# Signal_source_V1p0.net
KiCad netlist of a schematic drawn in EAGLE
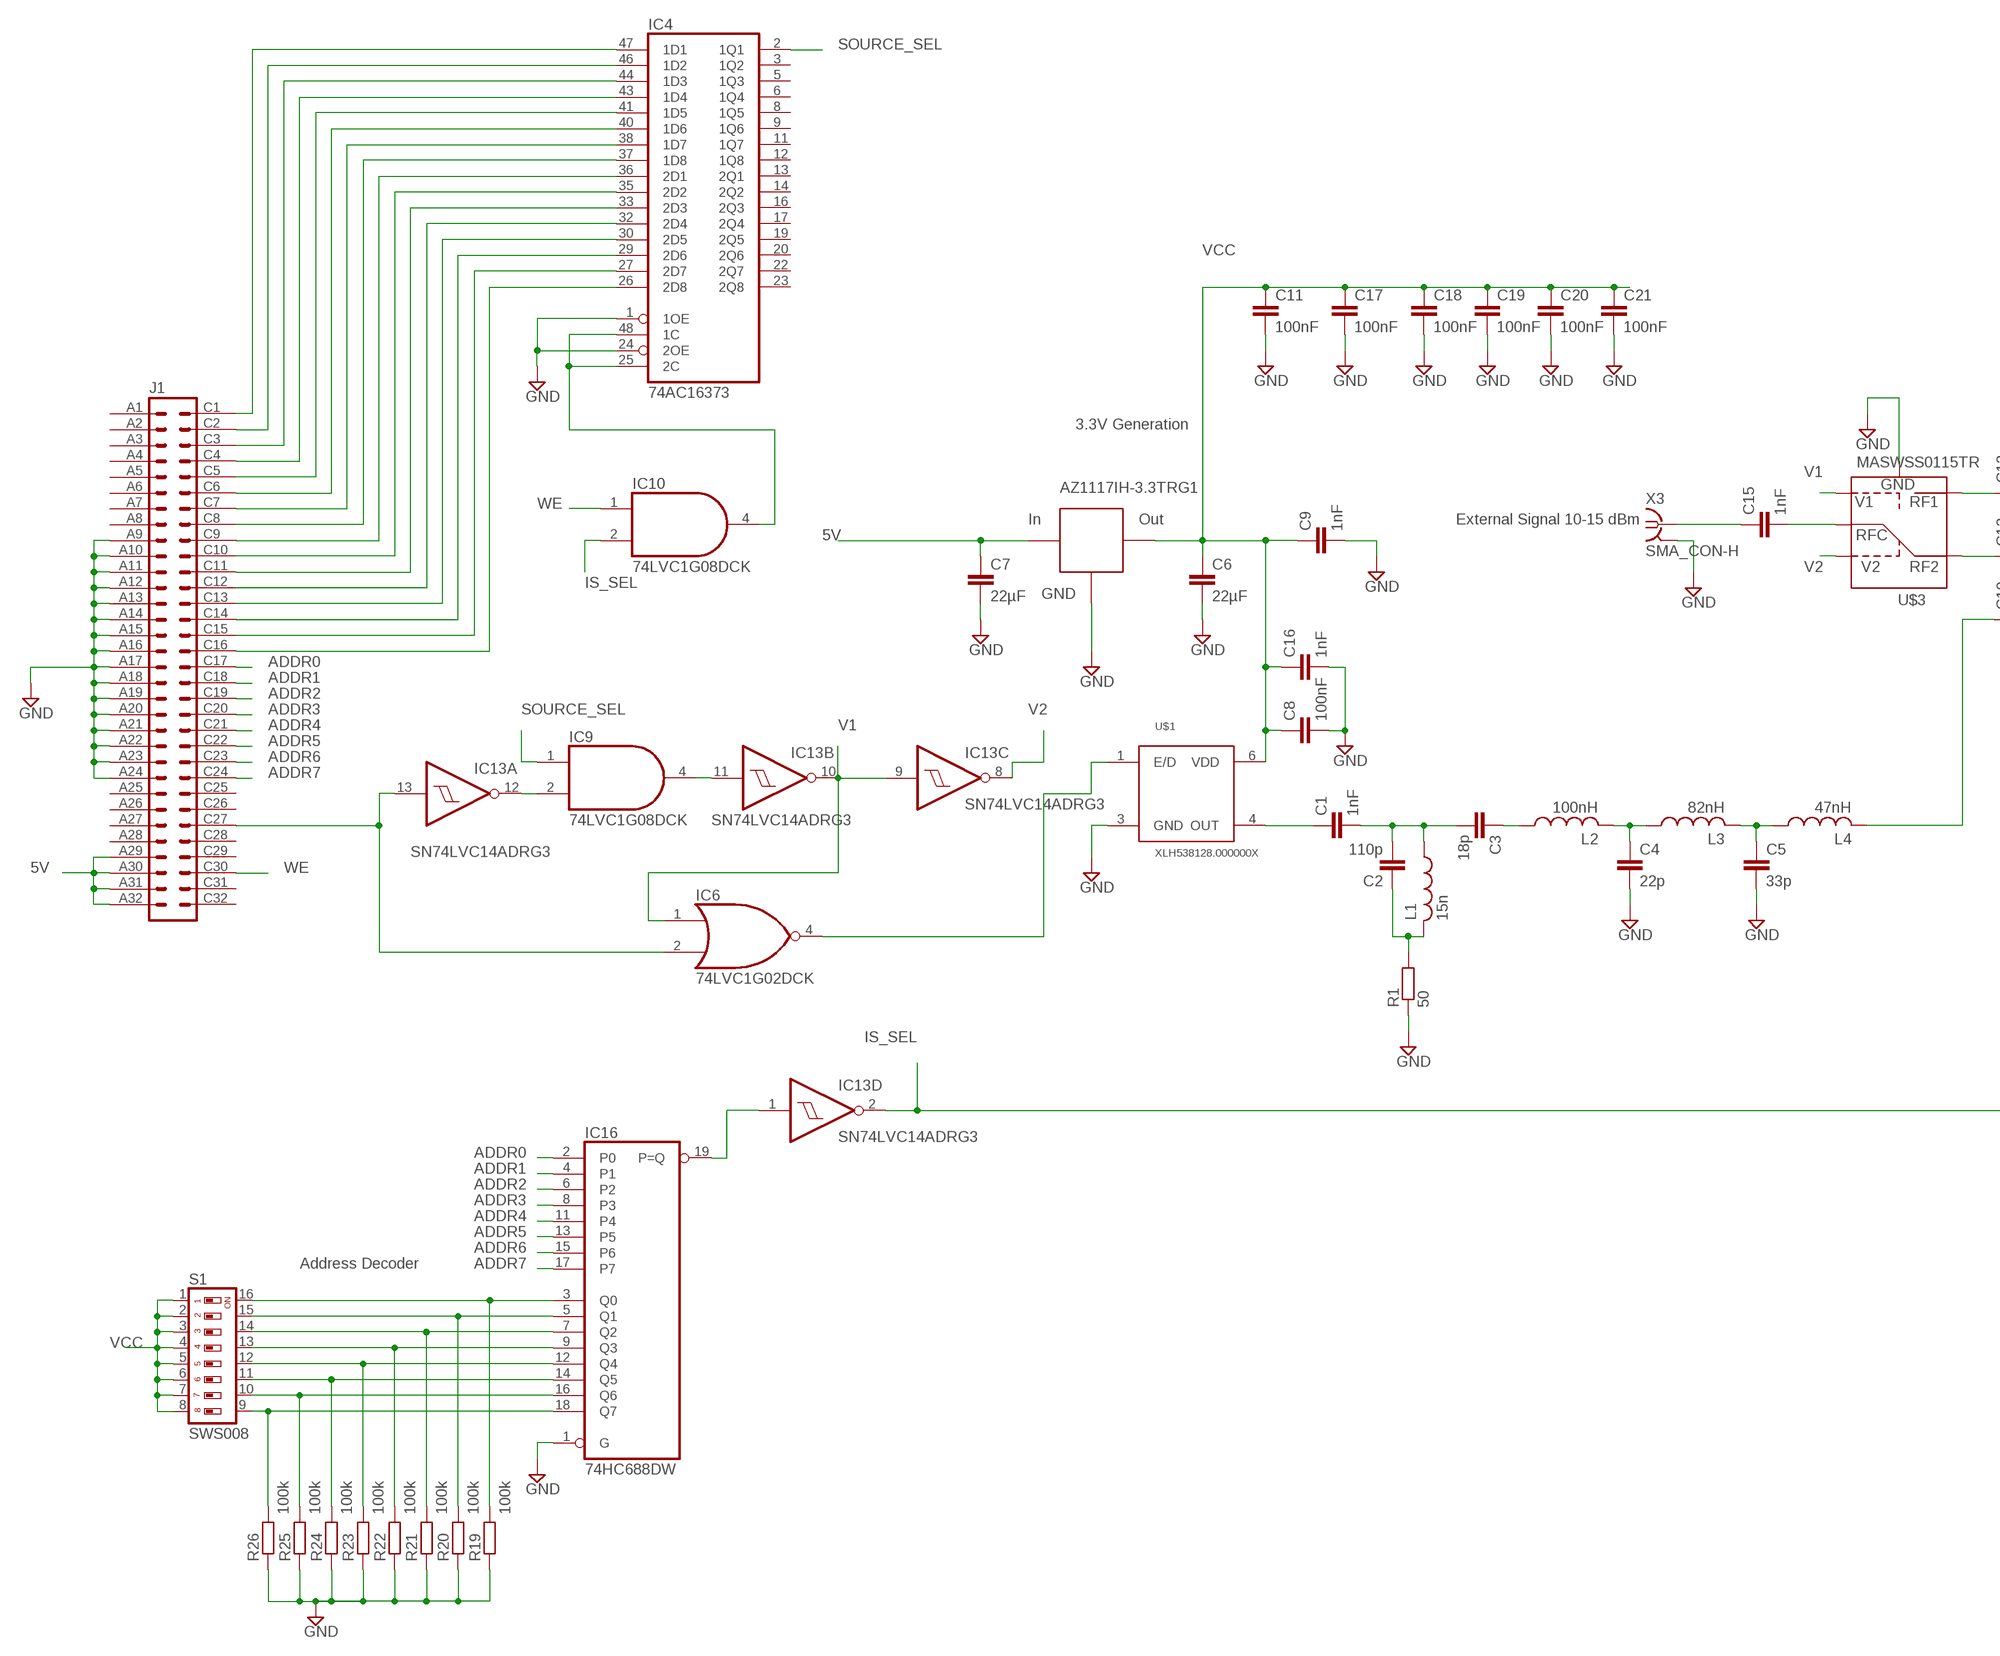
[diagram p0: schematic, sheet 1, part 1 of 2]
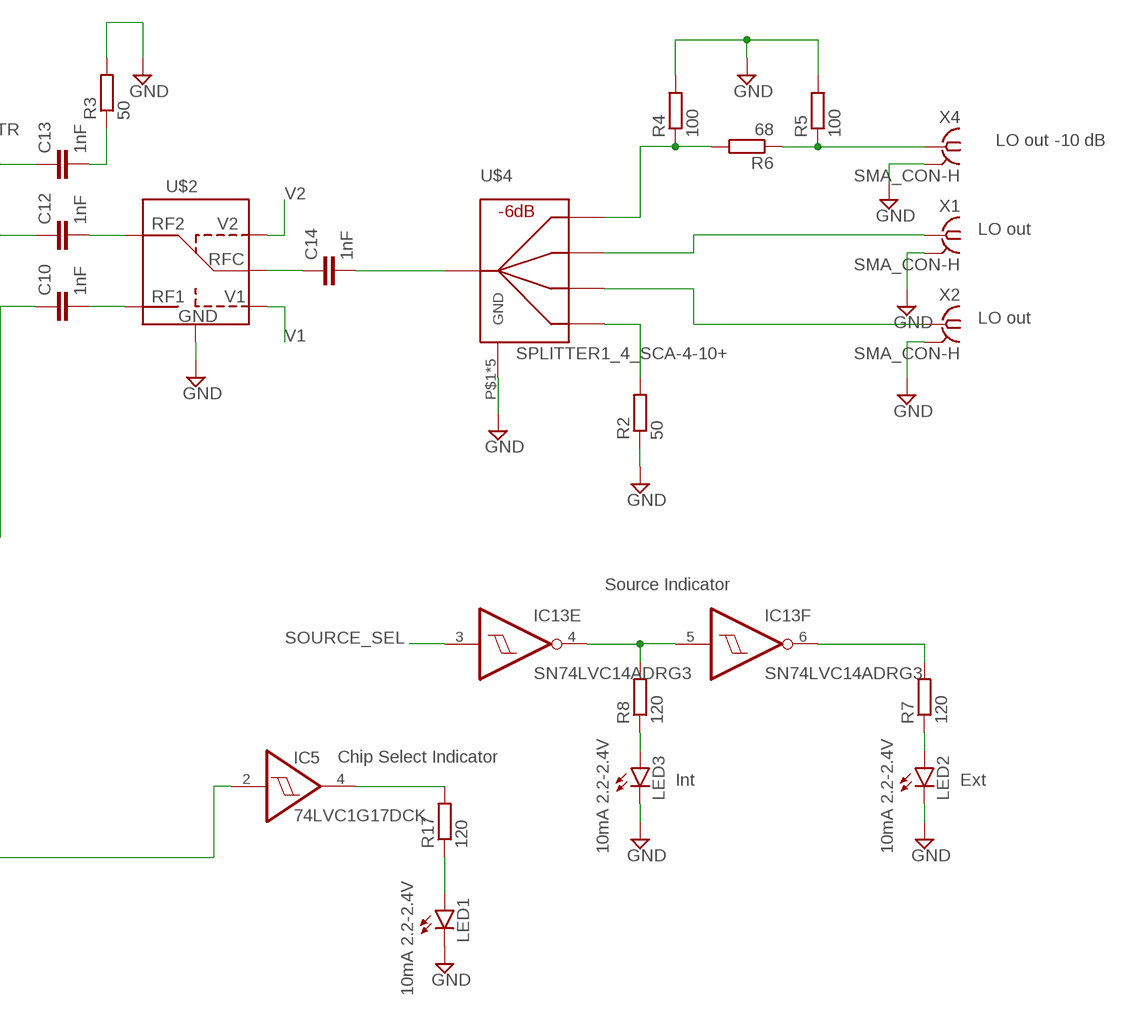
[diagram p1: schematic, sheet 1, part 2 of 2]

(export (version "E")
  (design (tool "Eeschema 10.0.6"))
  (components
    (comp (ref "C1")
      (value "1nF")
      (footprint "eagle-import:C0805")
      (libsource (lib "eagle-import") (part "C-EUC0805"))
    )
    (comp (ref "C2")
      (value "110p")
      (footprint "eagle-import:C0805")
      (libsource (lib "eagle-import") (part "C-EUC0805"))
    )
    (comp (ref "C3")
      (value "18p")
      (footprint "eagle-import:C0805")
      (libsource (lib "eagle-import") (part "C-EUC0805"))
    )
    (comp (ref "C4")
      (value "22p")
      (footprint "eagle-import:C0805")
      (libsource (lib "eagle-import") (part "C-EUC0805"))
    )
    (comp (ref "C5")
      (value "33p")
      (footprint "eagle-import:C0805")
      (libsource (lib "eagle-import") (part "C-EUC0805"))
    )
    (comp (ref "C6")
      (value "22µF")
      (footprint "eagle-import:C1206")
      (libsource (lib "eagle-import") (part "C-EUC1206"))
    )
    (comp (ref "C7")
      (value "22µF")
      (footprint "eagle-import:C1206")
      (libsource (lib "eagle-import") (part "C-EUC1206"))
    )
    (comp (ref "C8")
      (value "100nF")
      (footprint "eagle-import:C1206")
      (libsource (lib "eagle-import") (part "C-EUC1206"))
    )
    (comp (ref "C9")
      (value "1nF")
      (footprint "eagle-import:C0805")
      (libsource (lib "eagle-import") (part "C-EUC0805"))
    )
    (comp (ref "C10")
      (value "1nF")
      (footprint "eagle-import:C0805")
      (libsource (lib "eagle-import") (part "C-EUC0805"))
    )
    (comp (ref "C11")
      (value "100nF")
      (footprint "eagle-import:C1206")
      (libsource (lib "eagle-import") (part "C-EUC1206"))
    )
    (comp (ref "C12")
      (value "1nF")
      (footprint "eagle-import:C0805")
      (libsource (lib "eagle-import") (part "C-EUC0805"))
    )
    (comp (ref "C13")
      (value "1nF")
      (footprint "eagle-import:C0805")
      (libsource (lib "eagle-import") (part "C-EUC0805"))
    )
    (comp (ref "C14")
      (value "1nF")
      (footprint "eagle-import:C0805")
      (libsource (lib "eagle-import") (part "C-EUC0805"))
    )
    (comp (ref "C15")
      (value "1nF")
      (footprint "eagle-import:C0805")
      (libsource (lib "eagle-import") (part "C-EUC0805"))
    )
    (comp (ref "C16")
      (value "1nF")
      (footprint "eagle-import:C0805")
      (libsource (lib "eagle-import") (part "C-EUC0805"))
    )
    (comp (ref "C17")
      (value "100nF")
      (footprint "eagle-import:C1206")
      (libsource (lib "eagle-import") (part "C-EUC1206"))
    )
    (comp (ref "C18")
      (value "100nF")
      (footprint "eagle-import:C1206")
      (libsource (lib "eagle-import") (part "C-EUC1206"))
    )
    (comp (ref "C19")
      (value "100nF")
      (footprint "eagle-import:C1206")
      (libsource (lib "eagle-import") (part "C-EUC1206"))
    )
    (comp (ref "C20")
      (value "100nF")
      (footprint "eagle-import:C1206")
      (libsource (lib "eagle-import") (part "C-EUC1206"))
    )
    (comp (ref "C21")
      (value "100nF")
      (footprint "eagle-import:C1206")
      (libsource (lib "eagle-import") (part "C-EUC1206"))
    )
    (comp (ref "IC4")
      (value "74AC16373")
      (footprint "eagle-import:SSOP48DL")
      (libsource (lib "eagle-import") (part "74AC16373"))
    )
    (comp (ref "IC5")
      (value "74LVC1G17DCK")
      (footprint "eagle-import:SC70-5")
      (libsource (lib "eagle-import") (part "741G17DCKLVC"))
    )
    (comp (ref "IC6")
      (value "74LVC1G02DCK")
      (footprint "eagle-import:SC70-5")
      (libsource (lib "eagle-import") (part "741G02DCKLVC"))
    )
    (comp (ref "IC9")
      (value "74LVC1G08DCK")
      (footprint "eagle-import:SC70-5")
      (libsource (lib "eagle-import") (part "741G08DCKLVC"))
    )
    (comp (ref "IC10")
      (value "74LVC1G08DCK")
      (footprint "eagle-import:SC70-5")
      (libsource (lib "eagle-import") (part "741G08DCKLVC"))
    )
    (comp (ref "IC13")
      (value "SN74LVC14ADRG3")
      (footprint "eagle-import:SO14")
      (libsource (lib "eagle-import") (part "7414D"))
    )
    (comp (ref "IC16")
      (value "74HC688DW")
      (footprint "eagle-import:SO20W")
      (libsource (lib "eagle-import") (part "74688DWHC"))
    )
    (comp (ref "J1")
      (value "VG64P")
      (footprint "eagle-import:VG64P")
      (libsource (lib "eagle-import") (part "VG64P"))
    )
    (comp (ref "L1")
      (value "15n")
      (footprint "eagle-import:L3225M")
      (libsource (lib "eagle-import") (part "L-USL3225M"))
    )
    (comp (ref "L2")
      (value "100nH")
      (footprint "eagle-import:L3225M")
      (libsource (lib "eagle-import") (part "L-USL3225M"))
    )
    (comp (ref "L3")
      (value "82nH")
      (footprint "eagle-import:L3225M")
      (libsource (lib "eagle-import") (part "L-USL3225M"))
    )
    (comp (ref "L4")
      (value "47nH")
      (footprint "eagle-import:L3225M")
      (libsource (lib "eagle-import") (part "L-USL3225M"))
    )
    (comp (ref "LED1")
      (value "10mA 2.2-2.4V")
      (footprint "eagle-import:LED3MM")
      (libsource (lib "eagle-import") (part "LED3MM"))
    )
    (comp (ref "LED2")
      (value "10mA 2.2-2.4V")
      (footprint "eagle-import:LED3MM")
      (libsource (lib "eagle-import") (part "LED3MM"))
    )
    (comp (ref "LED3")
      (value "10mA 2.2-2.4V")
      (footprint "eagle-import:LED3MM")
      (libsource (lib "eagle-import") (part "LED3MM"))
    )
    (comp (ref "R1")
      (value "50")
      (footprint "eagle-import:R0805")
      (libsource (lib "eagle-import") (part "R-EU_R0805"))
    )
    (comp (ref "R2")
      (value "50")
      (footprint "eagle-import:R0805")
      (libsource (lib "eagle-import") (part "R-EU_R0805"))
    )
    (comp (ref "R3")
      (value "50")
      (footprint "eagle-import:R0805")
      (libsource (lib "eagle-import") (part "R-EU_R0805"))
    )
    (comp (ref "R4")
      (value "100")
      (footprint "eagle-import:R0805")
      (libsource (lib "eagle-import") (part "R-EU_R0805"))
    )
    (comp (ref "R5")
      (value "100")
      (footprint "eagle-import:R0805")
      (libsource (lib "eagle-import") (part "R-EU_R0805"))
    )
    (comp (ref "R6")
      (value "68")
      (footprint "eagle-import:R0805")
      (libsource (lib "eagle-import") (part "R-EU_R0805"))
    )
    (comp (ref "R7")
      (value "120")
      (footprint "eagle-import:R0603")
      (libsource (lib "eagle-import") (part "R-EU_R0603"))
    )
    (comp (ref "R8")
      (value "120")
      (footprint "eagle-import:R0603")
      (libsource (lib "eagle-import") (part "R-EU_R0603"))
    )
    (comp (ref "R17")
      (value "120")
      (footprint "eagle-import:R0603")
      (libsource (lib "eagle-import") (part "R-EU_R0603"))
    )
    (comp (ref "R19")
      (value "100k")
      (footprint "eagle-import:R0603")
      (libsource (lib "eagle-import") (part "R-EU_R0603"))
    )
    (comp (ref "R20")
      (value "100k")
      (footprint "eagle-import:R0603")
      (libsource (lib "eagle-import") (part "R-EU_R0603"))
    )
    (comp (ref "R21")
      (value "100k")
      (footprint "eagle-import:R0603")
      (libsource (lib "eagle-import") (part "R-EU_R0603"))
    )
    (comp (ref "R22")
      (value "100k")
      (footprint "eagle-import:R0603")
      (libsource (lib "eagle-import") (part "R-EU_R0603"))
    )
    (comp (ref "R23")
      (value "100k")
      (footprint "eagle-import:R0603")
      (libsource (lib "eagle-import") (part "R-EU_R0603"))
    )
    (comp (ref "R24")
      (value "100k")
      (footprint "eagle-import:R0603")
      (libsource (lib "eagle-import") (part "R-EU_R0603"))
    )
    (comp (ref "R25")
      (value "100k")
      (footprint "eagle-import:R0603")
      (libsource (lib "eagle-import") (part "R-EU_R0603"))
    )
    (comp (ref "R26")
      (value "100k")
      (footprint "eagle-import:R0603")
      (libsource (lib "eagle-import") (part "R-EU_R0603"))
    )
    (comp (ref "S1")
      (value "SWS008")
      (footprint "eagle-import:SMS-008")
      (libsource (lib "eagle-import") (part "SWS008"))
    )
    (comp (ref "U$1")
      (value "XLH538128.000000X")
      (footprint "eagle-import:5.0X3.2_XO")
      (libsource (lib "eagle-import") (part "XLH538128.000000X"))
    )
    (comp (ref "U$2")
      (value "MASWSS0115TR")
      (footprint "eagle-import:SC70-6")
      (libsource (lib "eagle-import") (part "SPDT_SC70-6"))
    )
    (comp (ref "U$3")
      (value "MASWSS0115TR")
      (footprint "eagle-import:SC70-6")
      (libsource (lib "eagle-import") (part "SPDT_SC70-6"))
    )
    (comp (ref "U$4")
      (value "SPLITTER1_4_SCA-4-10+")
      (footprint "eagle-import:SCA-4-10+")
      (libsource (lib "eagle-import") (part "SPLITTER1_4_SCA-4-10+"))
    )
    (comp (ref "U$9")
      (value "AZ1117IH-3.3TRG1")
      (footprint "eagle-import:SOT223")
      (libsource (lib "eagle-import") (part "LT1117"))
    )
    (comp (ref "X1")
      (value "SMA_CON-H")
      (footprint "eagle-import:BU-SMA-H")
      (libsource (lib "eagle-import") (part "SMA_CON-H"))
    )
    (comp (ref "X2")
      (value "SMA_CON-H")
      (footprint "eagle-import:BU-SMA-H")
      (libsource (lib "eagle-import") (part "SMA_CON-H"))
    )
    (comp (ref "X3")
      (value "SMA_CON-H")
      (footprint "eagle-import:BU-SMA-H")
      (libsource (lib "eagle-import") (part "SMA_CON-H"))
    )
    (comp (ref "X4")
      (value "SMA_CON-H")
      (footprint "eagle-import:BU-SMA-H")
      (libsource (lib "eagle-import") (part "SMA_CON-H"))
    )
  )
  (nets
    (net (code "1") (name "/5V") (class "Default")
      (node (ref "C7") (pin "1") (pinfunction "1_1") (pintype "passive"))
      (node (ref "J1") (pin "A29") (pinfunction "A29_A29") (pintype "passive"))
      (node (ref "J1") (pin "A30") (pinfunction "A30_A30") (pintype "passive"))
      (node (ref "J1") (pin "A31") (pinfunction "A31_A31") (pintype "passive"))
      (node (ref "J1") (pin "A32") (pinfunction "A32_A32") (pintype "passive"))
      (node (ref "U$9") (pin "3") (pinfunction "IN_3") (pintype "bidirectional"))
    )
    (net (code "2") (name "/ADDR0") (class "Default")
      (node (ref "IC16") (pin "2") (pinfunction "P0_2") (pintype "input"))
      (node (ref "J1") (pin "C17") (pinfunction "C17_C17") (pintype "passive"))
    )
    (net (code "3") (name "/ADDR1") (class "Default")
      (node (ref "IC16") (pin "4") (pinfunction "P1_4") (pintype "input"))
      (node (ref "J1") (pin "C18") (pinfunction "C18_C18") (pintype "passive"))
    )
    (net (code "4") (name "/ADDR2") (class "Default")
      (node (ref "IC16") (pin "6") (pinfunction "P2_6") (pintype "input"))
      (node (ref "J1") (pin "C19") (pinfunction "C19_C19") (pintype "passive"))
    )
    (net (code "5") (name "/ADDR3") (class "Default")
      (node (ref "IC16") (pin "8") (pinfunction "P3_8") (pintype "input"))
      (node (ref "J1") (pin "C20") (pinfunction "C20_C20") (pintype "passive"))
    )
    (net (code "6") (name "/ADDR4") (class "Default")
      (node (ref "IC16") (pin "11") (pinfunction "P4_11") (pintype "input"))
      (node (ref "J1") (pin "C21") (pinfunction "C21_C21") (pintype "passive"))
    )
    (net (code "7") (name "/ADDR5") (class "Default")
      (node (ref "IC16") (pin "13") (pinfunction "P5_13") (pintype "input"))
      (node (ref "J1") (pin "C22") (pinfunction "C22_C22") (pintype "passive"))
    )
    (net (code "8") (name "/ADDR6") (class "Default")
      (node (ref "IC16") (pin "15") (pinfunction "P6_15") (pintype "input"))
      (node (ref "J1") (pin "C23") (pinfunction "C23_C23") (pintype "passive"))
    )
    (net (code "9") (name "/ADDR7") (class "Default")
      (node (ref "IC16") (pin "17") (pinfunction "P7_17") (pintype "input"))
      (node (ref "J1") (pin "C24") (pinfunction "C24_C24") (pintype "passive"))
    )
    (net (code "10") (name "/IS_SEL") (class "Default")
      (node (ref "IC10") (pin "2") (pinfunction "I1_2") (pintype "input"))
      (node (ref "IC13") (pin "2") (pinfunction "O_2") (pintype "output"))
      (node (ref "IC5") (pin "2") (pinfunction "I_2") (pintype "input"))
    )
    (net (code "11") (name "/SOURCE_SEL") (class "Default")
      (node (ref "IC13") (pin "3") (pinfunction "I_3") (pintype "input"))
      (node (ref "IC4") (pin "2") (pinfunction "1Q1_2") (pintype "tri_state"))
      (node (ref "IC9") (pin "1") (pinfunction "I0_1") (pintype "input"))
    )
    (net (code "12") (name "/V1") (class "Default")
      (node (ref "IC13") (pin "10") (pinfunction "O_10") (pintype "output"))
      (node (ref "IC13") (pin "9") (pinfunction "I_9") (pintype "input"))
      (node (ref "IC6") (pin "1") (pinfunction "I0_1") (pintype "input"))
      (node (ref "U$2") (pin "6") (pinfunction "V1_6") (pintype "bidirectional"))
      (node (ref "U$3") (pin "6") (pinfunction "V1_6") (pintype "bidirectional"))
    )
    (net (code "13") (name "/V2") (class "Default")
      (node (ref "IC13") (pin "8") (pinfunction "O_8") (pintype "output"))
      (node (ref "U$2") (pin "4") (pinfunction "V2_4") (pintype "bidirectional"))
      (node (ref "U$3") (pin "4") (pinfunction "V2_4") (pintype "bidirectional"))
    )
    (net (code "14") (name "/VCC") (class "Default")
      (node (ref "C11") (pin "1") (pinfunction "1_1") (pintype "passive"))
      (node (ref "C16") (pin "1") (pinfunction "1_1") (pintype "passive"))
      (node (ref "C17") (pin "1") (pinfunction "1_1") (pintype "passive"))
      (node (ref "C18") (pin "1") (pinfunction "1_1") (pintype "passive"))
      (node (ref "C19") (pin "1") (pinfunction "1_1") (pintype "passive"))
      (node (ref "C20") (pin "1") (pinfunction "1_1") (pintype "passive"))
      (node (ref "C21") (pin "1") (pinfunction "1_1") (pintype "passive"))
      (node (ref "C6") (pin "1") (pinfunction "1_1") (pintype "passive"))
      (node (ref "C8") (pin "1") (pinfunction "1_1") (pintype "passive"))
      (node (ref "C9") (pin "1") (pinfunction "1_1") (pintype "passive"))
      (node (ref "S1") (pin "1") (pinfunction "1_1") (pintype "passive"))
      (node (ref "S1") (pin "2") (pinfunction "2_2") (pintype "passive"))
      (node (ref "S1") (pin "3") (pinfunction "3_3") (pintype "passive"))
      (node (ref "S1") (pin "4") (pinfunction "4_4") (pintype "passive"))
      (node (ref "S1") (pin "5") (pinfunction "5_5") (pintype "passive"))
      (node (ref "S1") (pin "6") (pinfunction "6_6") (pintype "passive"))
      (node (ref "S1") (pin "7") (pinfunction "7_7") (pintype "passive"))
      (node (ref "S1") (pin "8") (pinfunction "8_8") (pintype "passive"))
      (node (ref "U$1") (pin "6") (pinfunction "VDD_6") (pintype "bidirectional"))
      (node (ref "U$9") (pin "2") (pinfunction "OUT_2") (pintype "bidirectional"))
      (node (ref "U$9") (pin "4") (pinfunction "OUT_4") (pintype "bidirectional"))
    )
    (net (code "15") (name "/WE") (class "Default")
      (node (ref "IC10") (pin "1") (pinfunction "I0_1") (pintype "input"))
      (node (ref "J1") (pin "C30") (pinfunction "C30_C30") (pintype "passive"))
    )
    (net (code "16") (name "GND") (class "Default")
      (node (ref "C11") (pin "2") (pinfunction "2_2") (pintype "passive"))
      (node (ref "C16") (pin "2") (pinfunction "2_2") (pintype "passive"))
      (node (ref "C17") (pin "2") (pinfunction "2_2") (pintype "passive"))
      (node (ref "C18") (pin "2") (pinfunction "2_2") (pintype "passive"))
      (node (ref "C19") (pin "2") (pinfunction "2_2") (pintype "passive"))
      (node (ref "C20") (pin "2") (pinfunction "2_2") (pintype "passive"))
      (node (ref "C21") (pin "2") (pinfunction "2_2") (pintype "passive"))
      (node (ref "C4") (pin "2") (pinfunction "2_2") (pintype "passive"))
      (node (ref "C5") (pin "2") (pinfunction "2_2") (pintype "passive"))
      (node (ref "C6") (pin "2") (pinfunction "2_2") (pintype "passive"))
      (node (ref "C7") (pin "2") (pinfunction "2_2") (pintype "passive"))
      (node (ref "C8") (pin "2") (pinfunction "2_2") (pintype "passive"))
      (node (ref "C9") (pin "2") (pinfunction "2_2") (pintype "passive"))
      (node (ref "IC16") (pin "1") (pinfunction "G_1") (pintype "input"))
      (node (ref "IC4") (pin "1") (pinfunction "1OE_1") (pintype "input"))
      (node (ref "IC4") (pin "24") (pinfunction "2OE_24") (pintype "input"))
      (node (ref "J1") (pin "A10") (pinfunction "A10_A10") (pintype "passive"))
      (node (ref "J1") (pin "A11") (pinfunction "A11_A11") (pintype "passive"))
      (node (ref "J1") (pin "A12") (pinfunction "A12_A12") (pintype "passive"))
      (node (ref "J1") (pin "A13") (pinfunction "A13_A13") (pintype "passive"))
      (node (ref "J1") (pin "A14") (pinfunction "A14_A14") (pintype "passive"))
      (node (ref "J1") (pin "A15") (pinfunction "A15_A15") (pintype "passive"))
      (node (ref "J1") (pin "A16") (pinfunction "A16_A16") (pintype "passive"))
      (node (ref "J1") (pin "A17") (pinfunction "A17_A17") (pintype "passive"))
      (node (ref "J1") (pin "A18") (pinfunction "A18_A18") (pintype "passive"))
      (node (ref "J1") (pin "A19") (pinfunction "A19_A19") (pintype "passive"))
      (node (ref "J1") (pin "A20") (pinfunction "A20_A20") (pintype "passive"))
      (node (ref "J1") (pin "A21") (pinfunction "A21_A21") (pintype "passive"))
      (node (ref "J1") (pin "A22") (pinfunction "A22_A22") (pintype "passive"))
      (node (ref "J1") (pin "A23") (pinfunction "A23_A23") (pintype "passive"))
      (node (ref "J1") (pin "A24") (pinfunction "A24_A24") (pintype "passive"))
      (node (ref "J1") (pin "A9") (pinfunction "A9_A9") (pintype "passive"))
      (node (ref "LED1") (pin "K") (pinfunction "C_K") (pintype "passive"))
      (node (ref "LED2") (pin "K") (pinfunction "C_K") (pintype "passive"))
      (node (ref "LED3") (pin "K") (pinfunction "C_K") (pintype "passive"))
      (node (ref "R1") (pin "1") (pinfunction "1_1") (pintype "passive"))
      (node (ref "R19") (pin "1") (pinfunction "1_1") (pintype "passive"))
      (node (ref "R2") (pin "1") (pinfunction "1_1") (pintype "passive"))
      (node (ref "R20") (pin "1") (pinfunction "1_1") (pintype "passive"))
      (node (ref "R21") (pin "1") (pinfunction "1_1") (pintype "passive"))
      (node (ref "R22") (pin "1") (pinfunction "1_1") (pintype "passive"))
      (node (ref "R23") (pin "1") (pinfunction "1_1") (pintype "passive"))
      (node (ref "R24") (pin "1") (pinfunction "1_1") (pintype "passive"))
      (node (ref "R25") (pin "1") (pinfunction "1_1") (pintype "passive"))
      (node (ref "R26") (pin "1") (pinfunction "1_1") (pintype "passive"))
      (node (ref "R3") (pin "2") (pinfunction "2_2") (pintype "passive"))
      (node (ref "R4") (pin "2") (pinfunction "2_2") (pintype "passive"))
      (node (ref "R5") (pin "2") (pinfunction "2_2") (pintype "passive"))
      (node (ref "U$1") (pin "3") (pinfunction "GND_3") (pintype "bidirectional"))
      (node (ref "U$2") (pin "2") (pinfunction "GND_2") (pintype "bidirectional"))
      (node (ref "U$3") (pin "2") (pinfunction "GND_2") (pintype "bidirectional"))
      (node (ref "U$4") (pin "P$1") (pinfunction "GND_P$1") (pintype "bidirectional"))
      (node (ref "U$4") (pin "P$2") (pinfunction "GND_P$2") (pintype "bidirectional"))
      (node (ref "U$4") (pin "P$4") (pinfunction "GND_P$4") (pintype "bidirectional"))
      (node (ref "U$4") (pin "P$5") (pinfunction "GND_P$5") (pintype "bidirectional"))
      (node (ref "U$4") (pin "P$8") (pinfunction "GND_P$8") (pintype "bidirectional"))
      (node (ref "U$9") (pin "1") (pinfunction "GND_1") (pintype "bidirectional"))
      (node (ref "X1") (pin "2") (pinfunction "GND_2") (pintype "passive"))
      (node (ref "X1") (pin "3") (pinfunction "GND_3") (pintype "passive"))
      (node (ref "X1") (pin "4") (pinfunction "GND_4") (pintype "passive"))
      (node (ref "X1") (pin "5") (pinfunction "GND_5") (pintype "passive"))
      (node (ref "X2") (pin "2") (pinfunction "GND_2") (pintype "passive"))
      (node (ref "X2") (pin "3") (pinfunction "GND_3") (pintype "passive"))
      (node (ref "X2") (pin "4") (pinfunction "GND_4") (pintype "passive"))
      (node (ref "X2") (pin "5") (pinfunction "GND_5") (pintype "passive"))
      (node (ref "X3") (pin "2") (pinfunction "GND_2") (pintype "passive"))
      (node (ref "X3") (pin "3") (pinfunction "GND_3") (pintype "passive"))
      (node (ref "X3") (pin "4") (pinfunction "GND_4") (pintype "passive"))
      (node (ref "X3") (pin "5") (pinfunction "GND_5") (pintype "passive"))
      (node (ref "X4") (pin "2") (pinfunction "GND_2") (pintype "passive"))
      (node (ref "X4") (pin "3") (pinfunction "GND_3") (pintype "passive"))
      (node (ref "X4") (pin "4") (pinfunction "GND_4") (pintype "passive"))
      (node (ref "X4") (pin "5") (pinfunction "GND_5") (pintype "passive"))
    )
    (net (code "17") (name "Net-(C1-Pad2)") (class "Default")
      (node (ref "C1") (pin "2") (pinfunction "2_2") (pintype "passive"))
      (node (ref "C2") (pin "2") (pinfunction "2_2") (pintype "passive"))
      (node (ref "C3") (pin "2") (pinfunction "2_2") (pintype "passive"))
      (node (ref "L1") (pin "1") (pinfunction "1_1") (pintype "passive"))
    )
    (net (code "18") (name "Net-(C2-Pad1)") (class "Default")
      (node (ref "C2") (pin "1") (pinfunction "1_1") (pintype "passive"))
      (node (ref "L1") (pin "2") (pinfunction "2_2") (pintype "passive"))
      (node (ref "R1") (pin "2") (pinfunction "2_2") (pintype "passive"))
    )
    (net (code "19") (name "Net-(C3-Pad1)") (class "Default")
      (node (ref "C3") (pin "1") (pinfunction "1_1") (pintype "passive"))
      (node (ref "L2") (pin "1") (pinfunction "1_1") (pintype "passive"))
    )
    (net (code "20") (name "Net-(C4-Pad1)") (class "Default")
      (node (ref "C4") (pin "1") (pinfunction "1_1") (pintype "passive"))
      (node (ref "L2") (pin "2") (pinfunction "2_2") (pintype "passive"))
      (node (ref "L3") (pin "1") (pinfunction "1_1") (pintype "passive"))
    )
    (net (code "21") (name "Net-(C5-Pad1)") (class "Default")
      (node (ref "C5") (pin "1") (pinfunction "1_1") (pintype "passive"))
      (node (ref "L3") (pin "2") (pinfunction "2_2") (pintype "passive"))
      (node (ref "L4") (pin "1") (pinfunction "1_1") (pintype "passive"))
    )
    (net (code "22") (name "Net-(C10-Pad1)") (class "Default")
      (node (ref "C10") (pin "1") (pinfunction "1_1") (pintype "passive"))
      (node (ref "L4") (pin "2") (pinfunction "2_2") (pintype "passive"))
    )
    (net (code "23") (name "Net-(C13-Pad2)") (class "Default")
      (node (ref "C13") (pin "2") (pinfunction "2_2") (pintype "passive"))
      (node (ref "R3") (pin "1") (pinfunction "1_1") (pintype "passive"))
    )
    (net (code "24") (name "Net-(C15-Pad1)") (class "Default")
      (node (ref "C15") (pin "1") (pinfunction "1_1") (pintype "passive"))
      (node (ref "X3") (pin "1") (pinfunction "1_1") (pintype "passive"))
    )
    (net (code "25") (name "Net-(IC4A-1D1)") (class "Default")
      (node (ref "IC4") (pin "47") (pinfunction "1D1_47") (pintype "input"))
      (node (ref "J1") (pin "C1") (pinfunction "C1_C1") (pintype "passive"))
    )
    (net (code "26") (name "Net-(IC4A-1D2)") (class "Default")
      (node (ref "IC4") (pin "46") (pinfunction "1D2_46") (pintype "input"))
      (node (ref "J1") (pin "C2") (pinfunction "C2_C2") (pintype "passive"))
    )
    (net (code "27") (name "Net-(IC4A-1D3)") (class "Default")
      (node (ref "IC4") (pin "44") (pinfunction "1D3_44") (pintype "input"))
      (node (ref "J1") (pin "C3") (pinfunction "C3_C3") (pintype "passive"))
    )
    (net (code "28") (name "Net-(IC4A-1D4)") (class "Default")
      (node (ref "IC4") (pin "43") (pinfunction "1D4_43") (pintype "input"))
      (node (ref "J1") (pin "C4") (pinfunction "C4_C4") (pintype "passive"))
    )
    (net (code "29") (name "Net-(IC4A-1D5)") (class "Default")
      (node (ref "IC4") (pin "41") (pinfunction "1D5_41") (pintype "input"))
      (node (ref "J1") (pin "C5") (pinfunction "C5_C5") (pintype "passive"))
    )
    (net (code "30") (name "Net-(IC4A-1D6)") (class "Default")
      (node (ref "IC4") (pin "40") (pinfunction "1D6_40") (pintype "input"))
      (node (ref "J1") (pin "C6") (pinfunction "C6_C6") (pintype "passive"))
    )
    (net (code "31") (name "Net-(IC4A-1D7)") (class "Default")
      (node (ref "IC4") (pin "38") (pinfunction "1D7_38") (pintype "input"))
      (node (ref "J1") (pin "C7") (pinfunction "C7_C7") (pintype "passive"))
    )
    (net (code "32") (name "Net-(IC4A-1D8)") (class "Default")
      (node (ref "IC4") (pin "37") (pinfunction "1D8_37") (pintype "input"))
      (node (ref "J1") (pin "C8") (pinfunction "C8_C8") (pintype "passive"))
    )
    (net (code "33") (name "Net-(IC4A-2D1)") (class "Default")
      (node (ref "IC4") (pin "36") (pinfunction "2D1_36") (pintype "input"))
      (node (ref "J1") (pin "C9") (pinfunction "C9_C9") (pintype "passive"))
    )
    (net (code "34") (name "Net-(IC4A-2D2)") (class "Default")
      (node (ref "IC4") (pin "35") (pinfunction "2D2_35") (pintype "input"))
      (node (ref "J1") (pin "C10") (pinfunction "C10_C10") (pintype "passive"))
    )
    (net (code "35") (name "Net-(IC4A-2D3)") (class "Default")
      (node (ref "IC4") (pin "33") (pinfunction "2D3_33") (pintype "input"))
      (node (ref "J1") (pin "C11") (pinfunction "C11_C11") (pintype "passive"))
    )
    (net (code "36") (name "Net-(IC4A-2D4)") (class "Default")
      (node (ref "IC4") (pin "32") (pinfunction "2D4_32") (pintype "input"))
      (node (ref "J1") (pin "C12") (pinfunction "C12_C12") (pintype "passive"))
    )
    (net (code "37") (name "Net-(IC4A-2D5)") (class "Default")
      (node (ref "IC4") (pin "30") (pinfunction "2D5_30") (pintype "input"))
      (node (ref "J1") (pin "C13") (pinfunction "C13_C13") (pintype "passive"))
    )
    (net (code "38") (name "Net-(IC4A-2D6)") (class "Default")
      (node (ref "IC4") (pin "29") (pinfunction "2D6_29") (pintype "input"))
      (node (ref "J1") (pin "C14") (pinfunction "C14_C14") (pintype "passive"))
    )
    (net (code "39") (name "Net-(IC4A-2D7)") (class "Default")
      (node (ref "IC4") (pin "27") (pinfunction "2D7_27") (pintype "input"))
      (node (ref "J1") (pin "C15") (pinfunction "C15_C15") (pintype "passive"))
    )
    (net (code "40") (name "Net-(IC4A-2D8)") (class "Default")
      (node (ref "IC4") (pin "26") (pinfunction "2D8_26") (pintype "input"))
      (node (ref "J1") (pin "C16") (pinfunction "C16_C16") (pintype "passive"))
    )
    (net (code "41") (name "Net-(IC5A-O)") (class "Default")
      (node (ref "IC5") (pin "4") (pinfunction "O_4") (pintype "output"))
      (node (ref "R17") (pin "2") (pinfunction "2_2") (pintype "passive"))
    )
    (net (code "42") (name "Net-(IC6A-O)") (class "Default")
      (node (ref "IC6") (pin "4") (pinfunction "O_4") (pintype "output"))
      (node (ref "U$1") (pin "1") (pinfunction "E/D_1") (pintype "bidirectional"))
    )
    (net (code "43") (name "Net-(IC10A-O)") (class "Default")
      (node (ref "IC10") (pin "4") (pinfunction "O_4") (pintype "output"))
      (node (ref "IC4") (pin "25") (pinfunction "2C_25") (pintype "input"))
      (node (ref "IC4") (pin "48") (pinfunction "1C_48") (pintype "input"))
    )
    (net (code "44") (name "Net-(IC13A-I)") (class "Default")
      (node (ref "IC13") (pin "13") (pinfunction "I_13") (pintype "input"))
      (node (ref "IC6") (pin "2") (pinfunction "I1_2") (pintype "input"))
      (node (ref "J1") (pin "C27") (pinfunction "C27_C27") (pintype "passive"))
    )
    (net (code "45") (name "Net-(IC13A-O)") (class "Default")
      (node (ref "IC13") (pin "12") (pinfunction "O_12") (pintype "output"))
      (node (ref "IC9") (pin "2") (pinfunction "I1_2") (pintype "input"))
    )
    (net (code "46") (name "Net-(IC13B-I)") (class "Default")
      (node (ref "IC13") (pin "11") (pinfunction "I_11") (pintype "input"))
      (node (ref "IC9") (pin "4") (pinfunction "O_4") (pintype "output"))
    )
    (net (code "47") (name "Net-(IC13D-I)") (class "Default")
      (node (ref "IC13") (pin "1") (pinfunction "I_1") (pintype "input"))
      (node (ref "IC16") (pin "19") (pinfunction "P=Q_19") (pintype "output"))
    )
    (net (code "48") (name "Net-(IC13E-O)") (class "Default")
      (node (ref "IC13") (pin "4") (pinfunction "O_4") (pintype "output"))
      (node (ref "IC13") (pin "5") (pinfunction "I_5") (pintype "input"))
      (node (ref "R8") (pin "2") (pinfunction "2_2") (pintype "passive"))
    )
    (net (code "49") (name "Net-(IC13F-O)") (class "Default")
      (node (ref "IC13") (pin "6") (pinfunction "O_6") (pintype "output"))
      (node (ref "R7") (pin "2") (pinfunction "2_2") (pintype "passive"))
    )
    (net (code "50") (name "Net-(IC16A-Q0)") (class "Default")
      (node (ref "IC16") (pin "3") (pinfunction "Q0_3") (pintype "input"))
      (node (ref "R19") (pin "2") (pinfunction "2_2") (pintype "passive"))
      (node (ref "S1") (pin "16") (pinfunction "16_16") (pintype "passive"))
    )
    (net (code "51") (name "Net-(IC16A-Q1)") (class "Default")
      (node (ref "IC16") (pin "5") (pinfunction "Q1_5") (pintype "input"))
      (node (ref "R20") (pin "2") (pinfunction "2_2") (pintype "passive"))
      (node (ref "S1") (pin "15") (pinfunction "15_15") (pintype "passive"))
    )
    (net (code "52") (name "Net-(IC16A-Q2)") (class "Default")
      (node (ref "IC16") (pin "7") (pinfunction "Q2_7") (pintype "input"))
      (node (ref "R21") (pin "2") (pinfunction "2_2") (pintype "passive"))
      (node (ref "S1") (pin "14") (pinfunction "14_14") (pintype "passive"))
    )
    (net (code "53") (name "Net-(IC16A-Q3)") (class "Default")
      (node (ref "IC16") (pin "9") (pinfunction "Q3_9") (pintype "input"))
      (node (ref "R22") (pin "2") (pinfunction "2_2") (pintype "passive"))
      (node (ref "S1") (pin "13") (pinfunction "13_13") (pintype "passive"))
    )
    (net (code "54") (name "Net-(IC16A-Q4)") (class "Default")
      (node (ref "IC16") (pin "12") (pinfunction "Q4_12") (pintype "input"))
      (node (ref "R23") (pin "2") (pinfunction "2_2") (pintype "passive"))
      (node (ref "S1") (pin "12") (pinfunction "12_12") (pintype "passive"))
    )
    (net (code "55") (name "Net-(IC16A-Q5)") (class "Default")
      (node (ref "IC16") (pin "14") (pinfunction "Q5_14") (pintype "input"))
      (node (ref "R24") (pin "2") (pinfunction "2_2") (pintype "passive"))
      (node (ref "S1") (pin "11") (pinfunction "11_11") (pintype "passive"))
    )
    (net (code "56") (name "Net-(IC16A-Q6)") (class "Default")
      (node (ref "IC16") (pin "16") (pinfunction "Q6_16") (pintype "input"))
      (node (ref "R25") (pin "2") (pinfunction "2_2") (pintype "passive"))
      (node (ref "S1") (pin "10") (pinfunction "10_10") (pintype "passive"))
    )
    (net (code "57") (name "Net-(IC16A-Q7)") (class "Default")
      (node (ref "IC16") (pin "18") (pinfunction "Q7_18") (pintype "input"))
      (node (ref "R26") (pin "2") (pinfunction "2_2") (pintype "passive"))
      (node (ref "S1") (pin "9") (pinfunction "9_9") (pintype "passive"))
    )
    (net (code "58") (name "Net-(LED1-PadA)") (class "Default")
      (node (ref "LED1") (pin "A") (pinfunction "A_A") (pintype "passive"))
      (node (ref "R17") (pin "1") (pinfunction "1_1") (pintype "passive"))
    )
    (net (code "59") (name "Net-(LED2-PadA)") (class "Default")
      (node (ref "LED2") (pin "A") (pinfunction "A_A") (pintype "passive"))
      (node (ref "R7") (pin "1") (pinfunction "1_1") (pintype "passive"))
    )
    (net (code "60") (name "Net-(LED3-PadA)") (class "Default")
      (node (ref "LED3") (pin "A") (pinfunction "A_A") (pintype "passive"))
      (node (ref "R8") (pin "1") (pinfunction "1_1") (pintype "passive"))
    )
    (net (code "61") (name "Net-(R5-Pad1)") (class "Default")
      (node (ref "R5") (pin "1") (pinfunction "1_1") (pintype "passive"))
      (node (ref "R6") (pin "1") (pinfunction "1_1") (pintype "passive"))
      (node (ref "X4") (pin "1") (pinfunction "1_1") (pintype "passive"))
    )
    (net (code "62") (name "Net-(U$1-OUT)") (class "Default")
      (node (ref "C1") (pin "1") (pinfunction "1_1") (pintype "passive"))
      (node (ref "U$1") (pin "4") (pinfunction "OUT_4") (pintype "bidirectional"))
    )
    (net (code "63") (name "Net-(U$2-RF1)") (class "Default")
      (node (ref "C10") (pin "2") (pinfunction "2_2") (pintype "passive"))
      (node (ref "U$2") (pin "1") (pinfunction "RF1_1") (pintype "bidirectional"))
    )
    (net (code "64") (name "Net-(U$2-RF2)") (class "Default")
      (node (ref "C12") (pin "2") (pinfunction "2_2") (pintype "passive"))
      (node (ref "U$2") (pin "3") (pinfunction "RF2_3") (pintype "bidirectional"))
    )
    (net (code "65") (name "Net-(U$2-RFC)") (class "Default")
      (node (ref "C14") (pin "1") (pinfunction "1_1") (pintype "passive"))
      (node (ref "U$2") (pin "5") (pinfunction "RFC_5") (pintype "bidirectional"))
    )
    (net (code "66") (name "Net-(U$3-RF1)") (class "Default")
      (node (ref "C13") (pin "1") (pinfunction "1_1") (pintype "passive"))
      (node (ref "U$3") (pin "1") (pinfunction "RF1_1") (pintype "bidirectional"))
    )
    (net (code "67") (name "Net-(U$3-RF2)") (class "Default")
      (node (ref "C12") (pin "1") (pinfunction "1_1") (pintype "passive"))
      (node (ref "U$3") (pin "3") (pinfunction "RF2_3") (pintype "bidirectional"))
    )
    (net (code "68") (name "Net-(U$3-RFC)") (class "Default")
      (node (ref "C15") (pin "2") (pinfunction "2_2") (pintype "passive"))
      (node (ref "U$3") (pin "5") (pinfunction "RFC_5") (pintype "bidirectional"))
    )
    (net (code "69") (name "Net-(U$4-P$1)") (class "Default")
      (node (ref "C14") (pin "2") (pinfunction "2_2") (pintype "passive"))
      (node (ref "U$4") (pin "P$3") (pinfunction "P$1_P$3") (pintype "bidirectional"))
    )
    (net (code "70") (name "Net-(U$4-P$2)") (class "Default")
      (node (ref "R4") (pin "1") (pinfunction "1_1") (pintype "passive"))
      (node (ref "R6") (pin "2") (pinfunction "2_2") (pintype "passive"))
      (node (ref "U$4") (pin "P$6") (pinfunction "P$2_P$6") (pintype "bidirectional"))
    )
    (net (code "71") (name "Net-(U$4-P$3)") (class "Default")
      (node (ref "U$4") (pin "P$7") (pinfunction "P$3_P$7") (pintype "bidirectional"))
      (node (ref "X1") (pin "1") (pinfunction "1_1") (pintype "passive"))
    )
    (net (code "72") (name "Net-(U$4-P$4)") (class "Default")
      (node (ref "U$4") (pin "P$9") (pinfunction "P$4_P$9") (pintype "bidirectional"))
      (node (ref "X2") (pin "1") (pinfunction "1_1") (pintype "passive"))
    )
    (net (code "73") (name "Net-(U$4-P$5)") (class "Default")
      (node (ref "R2") (pin "2") (pinfunction "2_2") (pintype "passive"))
      (node (ref "U$4") (pin "P$10") (pinfunction "P$5_P$10") (pintype "bidirectional"))
    )
    (net (code "74") (name "unconnected-(IC4A-1Q2-Pad3)") (class "Default")
      (node (ref "IC4") (pin "3") (pinfunction "1Q2_3") (pintype "tri_state"))
    )
    (net (code "75") (name "unconnected-(IC4A-1Q3-Pad5)") (class "Default")
      (node (ref "IC4") (pin "5") (pinfunction "1Q3_5") (pintype "tri_state"))
    )
    (net (code "76") (name "unconnected-(IC4A-1Q4-Pad6)") (class "Default")
      (node (ref "IC4") (pin "6") (pinfunction "1Q4_6") (pintype "tri_state"))
    )
    (net (code "77") (name "unconnected-(IC4A-1Q5-Pad8)") (class "Default")
      (node (ref "IC4") (pin "8") (pinfunction "1Q5_8") (pintype "tri_state"))
    )
    (net (code "78") (name "unconnected-(IC4A-1Q6-Pad9)") (class "Default")
      (node (ref "IC4") (pin "9") (pinfunction "1Q6_9") (pintype "tri_state"))
    )
    (net (code "79") (name "unconnected-(IC4A-1Q7-Pad11)") (class "Default")
      (node (ref "IC4") (pin "11") (pinfunction "1Q7_11") (pintype "tri_state"))
    )
    (net (code "80") (name "unconnected-(IC4A-1Q8-Pad12)") (class "Default")
      (node (ref "IC4") (pin "12") (pinfunction "1Q8_12") (pintype "tri_state"))
    )
    (net (code "81") (name "unconnected-(IC4A-2Q1-Pad13)") (class "Default")
      (node (ref "IC4") (pin "13") (pinfunction "2Q1_13") (pintype "tri_state"))
    )
    (net (code "82") (name "unconnected-(IC4A-2Q2-Pad14)") (class "Default")
      (node (ref "IC4") (pin "14") (pinfunction "2Q2_14") (pintype "tri_state"))
    )
    (net (code "83") (name "unconnected-(IC4A-2Q3-Pad16)") (class "Default")
      (node (ref "IC4") (pin "16") (pinfunction "2Q3_16") (pintype "tri_state"))
    )
    (net (code "84") (name "unconnected-(IC4A-2Q4-Pad17)") (class "Default")
      (node (ref "IC4") (pin "17") (pinfunction "2Q4_17") (pintype "tri_state"))
    )
    (net (code "85") (name "unconnected-(IC4A-2Q5-Pad19)") (class "Default")
      (node (ref "IC4") (pin "19") (pinfunction "2Q5_19") (pintype "tri_state"))
    )
    (net (code "86") (name "unconnected-(IC4A-2Q6-Pad20)") (class "Default")
      (node (ref "IC4") (pin "20") (pinfunction "2Q6_20") (pintype "tri_state"))
    )
    (net (code "87") (name "unconnected-(IC4A-2Q7-Pad22)") (class "Default")
      (node (ref "IC4") (pin "22") (pinfunction "2Q7_22") (pintype "tri_state"))
    )
    (net (code "88") (name "unconnected-(IC4A-2Q8-Pad23)") (class "Default")
      (node (ref "IC4") (pin "23") (pinfunction "2Q8_23") (pintype "tri_state"))
    )
    (net (code "89") (name "unconnected-(J1-PadA1)") (class "Default")
      (node (ref "J1") (pin "A1") (pinfunction "A1_A1") (pintype "passive"))
    )
    (net (code "90") (name "unconnected-(J1-PadA2)") (class "Default")
      (node (ref "J1") (pin "A2") (pinfunction "A2_A2") (pintype "passive"))
    )
    (net (code "91") (name "unconnected-(J1-PadA3)") (class "Default")
      (node (ref "J1") (pin "A3") (pinfunction "A3_A3") (pintype "passive"))
    )
    (net (code "92") (name "unconnected-(J1-PadA4)") (class "Default")
      (node (ref "J1") (pin "A4") (pinfunction "A4_A4") (pintype "passive"))
    )
    (net (code "93") (name "unconnected-(J1-PadA5)") (class "Default")
      (node (ref "J1") (pin "A5") (pinfunction "A5_A5") (pintype "passive"))
    )
    (net (code "94") (name "unconnected-(J1-PadA6)") (class "Default")
      (node (ref "J1") (pin "A6") (pinfunction "A6_A6") (pintype "passive"))
    )
    (net (code "95") (name "unconnected-(J1-PadA7)") (class "Default")
      (node (ref "J1") (pin "A7") (pinfunction "A7_A7") (pintype "passive"))
    )
    (net (code "96") (name "unconnected-(J1-PadA8)") (class "Default")
      (node (ref "J1") (pin "A8") (pinfunction "A8_A8") (pintype "passive"))
    )
    (net (code "97") (name "unconnected-(J1-PadA25)") (class "Default")
      (node (ref "J1") (pin "A25") (pinfunction "A25_A25") (pintype "passive"))
    )
    (net (code "98") (name "unconnected-(J1-PadA26)") (class "Default")
      (node (ref "J1") (pin "A26") (pinfunction "A26_A26") (pintype "passive"))
    )
    (net (code "99") (name "unconnected-(J1-PadA27)") (class "Default")
      (node (ref "J1") (pin "A27") (pinfunction "A27_A27") (pintype "passive"))
    )
    (net (code "100") (name "unconnected-(J1-PadA28)") (class "Default")
      (node (ref "J1") (pin "A28") (pinfunction "A28_A28") (pintype "passive"))
    )
    (net (code "101") (name "unconnected-(J1-PadC25)") (class "Default")
      (node (ref "J1") (pin "C25") (pinfunction "C25_C25") (pintype "passive"))
    )
    (net (code "102") (name "unconnected-(J1-PadC26)") (class "Default")
      (node (ref "J1") (pin "C26") (pinfunction "C26_C26") (pintype "passive"))
    )
    (net (code "103") (name "unconnected-(J1-PadC28)") (class "Default")
      (node (ref "J1") (pin "C28") (pinfunction "C28_C28") (pintype "passive"))
    )
    (net (code "104") (name "unconnected-(J1-PadC29)") (class "Default")
      (node (ref "J1") (pin "C29") (pinfunction "C29_C29") (pintype "passive"))
    )
    (net (code "105") (name "unconnected-(J1-PadC31)") (class "Default")
      (node (ref "J1") (pin "C31") (pinfunction "C31_C31") (pintype "passive"))
    )
    (net (code "106") (name "unconnected-(J1-PadC32)") (class "Default")
      (node (ref "J1") (pin "C32") (pinfunction "C32_C32") (pintype "passive"))
    )
  )
)
